# design.net
KiCad netlist of a schematic drawn in Altium Designer
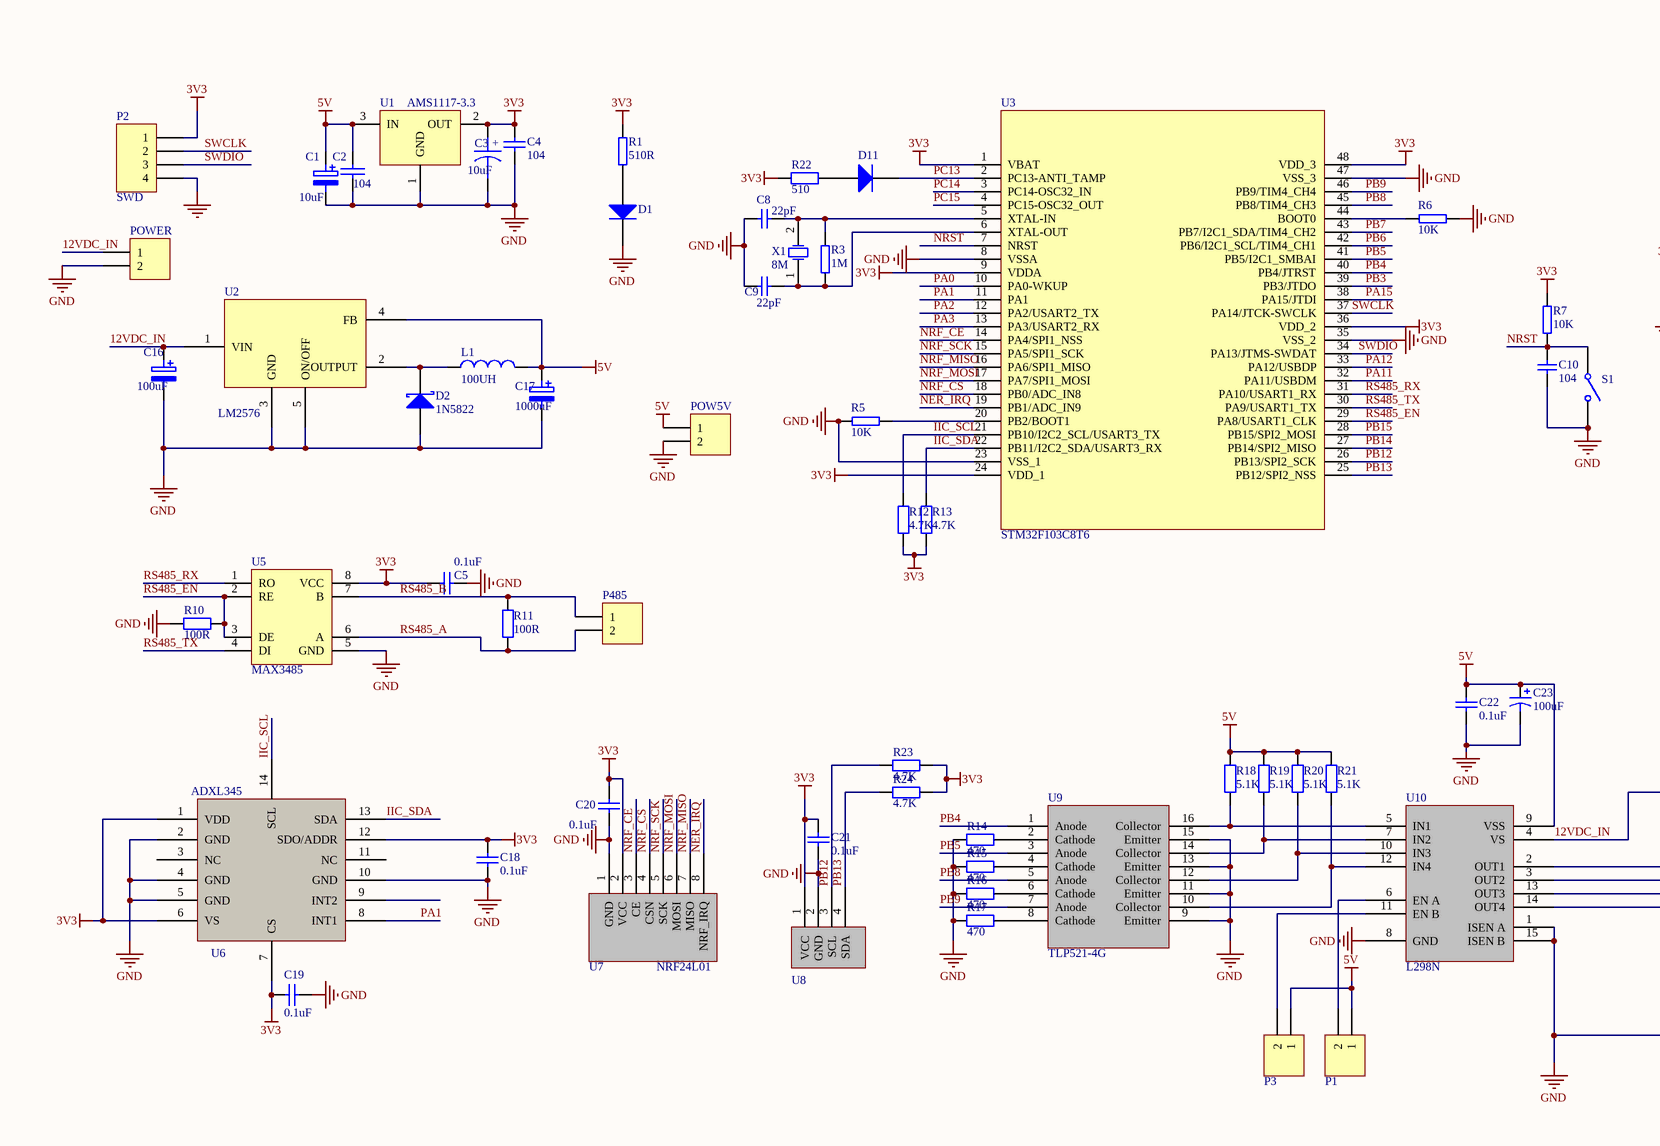
[diagram p0: 智能小车.SchDoc, left]
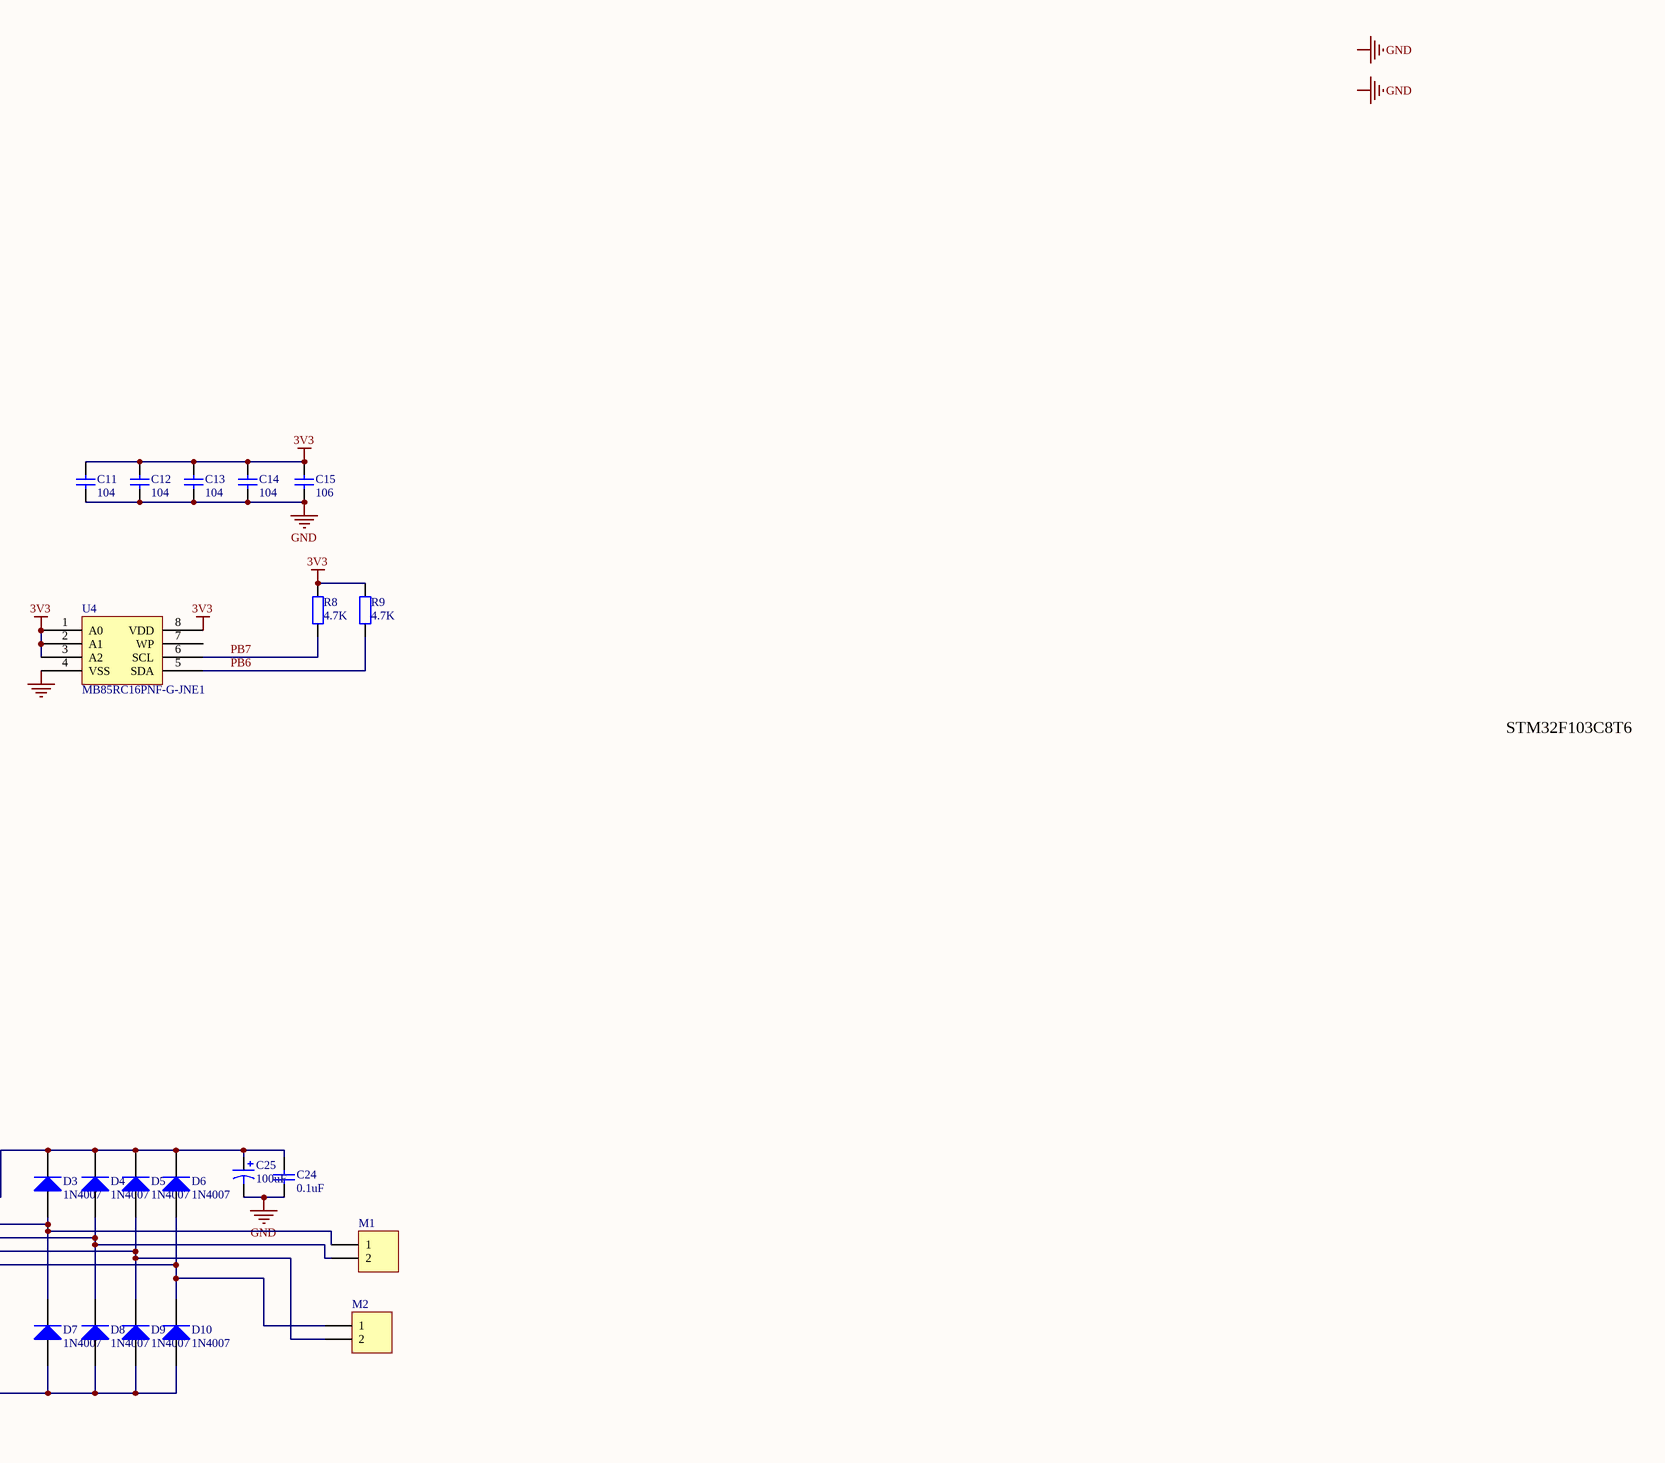
[diagram p1: 智能小车.SchDoc, right]

(export (version "E")
  (design (tool "Eeschema 10.0.6"))
  (components
    (comp (ref "C1") (value "10uF") (footprint "3216") (libsource (lib "*") (part "ELECTRO2")))
    (comp (ref "C2")
      (value "104")
      (footprint "0805")
      (description "Capacitor")
      (libsource (lib "*") (part "CAP"))
    )
    (comp (ref "C3")
      (value "10uF")
      (footprint "3216")
      (description "Capacitor")
      (libsource (lib "*") (part "CAPACITOR POL"))
    )
    (comp (ref "C4")
      (value "104")
      (footprint "0805")
      (description "Capacitor")
      (fields (field (name "PUBLISHER") "Altium Limited"))
      (libsource (lib "*") (part "Cap"))
    )
    (comp (ref "C5")
      (value "0.1uF")
      (footprint "0805")
      (description "Capacitor")
      (fields (field (name "Comment") "无源贴片电容") (field (name "PUBLISHER") "Altium Limited"))
      (libsource (lib "Miscellaneous Devices") (part "Cap"))
    )
    (comp (ref "C8")
      (value "22pF")
      (footprint "0805")
      (description "Capacitor")
      (fields (field (name "PUBLISHER") "ZL_A0OFFICE"))
      (libsource (lib "CommomDevices") (part "CAP1"))
    )
    (comp (ref "C9")
      (value "22pF")
      (footprint "0805")
      (description "Capacitor")
      (fields (field (name "PUBLISHER") "ZL_A0OFFICE"))
      (libsource (lib "CommomDevices") (part "CAP1"))
    )
    (comp (ref "C10")
      (value "104")
      (footprint "0805")
      (description "Capacitor")
      (fields (field (name "PUBLISHER") "ZL_A0OFFICE"))
      (libsource (lib "CommomDevices") (part "CAP1"))
    )
    (comp (ref "C11")
      (value "104")
      (footprint "0805")
      (description "Capacitor")
      (fields (field (name "PUBLISHER") "ZL_A0OFFICE"))
      (libsource (lib "CommomDevices") (part "CAP1"))
    )
    (comp (ref "C12")
      (value "104")
      (footprint "0805")
      (description "Capacitor")
      (fields (field (name "PUBLISHER") "ZL_A0OFFICE"))
      (libsource (lib "CommomDevices") (part "CAP1"))
    )
    (comp (ref "C13")
      (value "104")
      (footprint "0805")
      (description "Capacitor")
      (fields (field (name "PUBLISHER") "ZL_A0OFFICE"))
      (libsource (lib "CommomDevices") (part "CAP1"))
    )
    (comp (ref "C14")
      (value "104")
      (footprint "0805")
      (description "Capacitor")
      (fields (field (name "PUBLISHER") "ZL_A0OFFICE"))
      (libsource (lib "CommomDevices") (part "CAP1"))
    )
    (comp (ref "C15")
      (value "106")
      (footprint "0805")
      (description "Capacitor")
      (fields (field (name "PUBLISHER") "ZL_A0OFFICE"))
      (libsource (lib "CommomDevices") (part "CAP1"))
    )
    (comp (ref "C16") (value "100uF") (footprint "DIP2SMD") (libsource (lib "*") (part "ELECTRO2")))
    (comp (ref "C17") (value "1000uF") (footprint "DIP2SMD") (libsource (lib "*") (part "ELECTRO2")))
    (comp (ref "C18")
      (value "0.1uF")
      (footprint "0805")
      (description "Capacitor")
      (fields (field (name "Comment") "无源贴片电容") (field (name "PUBLISHER") "Altium Limited"))
      (libsource (lib "Miscellaneous Devices") (part "Cap"))
    )
    (comp (ref "C19")
      (value "0.1uF")
      (footprint "0805")
      (description "Capacitor")
      (fields (field (name "Comment") "无源贴片电容") (field (name "PUBLISHER") "Altium Limited"))
      (libsource (lib "Miscellaneous Devices") (part "Cap"))
    )
    (comp (ref "C20")
      (value "0.1uF")
      (footprint "0805")
      (description "Capacitor")
      (fields (field (name "Comment") "无源贴片电容") (field (name "PUBLISHER") "Altium Limited"))
      (libsource (lib "Miscellaneous Devices") (part "Cap"))
    )
    (comp (ref "C21")
      (value "0.1uF")
      (footprint "0805")
      (description "Capacitor")
      (fields (field (name "Comment") "无源贴片电容") (field (name "PUBLISHER") "Altium Limited"))
      (libsource (lib "Miscellaneous Devices") (part "Cap"))
    )
    (comp (ref "C22")
      (value "0.1uF")
      (footprint "0805")
      (description "Capacitor")
      (fields (field (name "Comment") "无源贴片电容") (field (name "PUBLISHER") "Altium Limited"))
      (libsource (lib "Miscellaneous Devices") (part "Cap"))
    )
    (comp (ref "C23")
      (value "100uF")
      (footprint "DIP2SMD")
      (description "Polarized Capacitor (Radial)")
      (fields (field (name "Comment") "Cap Pol1") (field (name "PUBLISHER") "Altium Limited"))
      (libsource (lib "Miscellaneous Devices") (part "Cap Pol1"))
    )
    (comp (ref "C24")
      (value "0.1uF")
      (footprint "0805")
      (description "Capacitor")
      (fields (field (name "Comment") "无源贴片电容") (field (name "PUBLISHER") "Altium Limited"))
      (libsource (lib "Miscellaneous Devices") (part "Cap"))
    )
    (comp (ref "C25")
      (value "100uF")
      (footprint "DIP2SMD")
      (description "Polarized Capacitor (Radial)")
      (fields (field (name "Comment") "Cap Pol1") (field (name "PUBLISHER") "Altium Limited"))
      (libsource (lib "Miscellaneous Devices") (part "Cap Pol1"))
    )
    (comp (ref "D1")
      (value "Diode")
      (footprint "LED")
      (description "Default Diode")
      (fields (field (name "PUBLISHER") "Altium Limited"))
      (libsource (lib "Miscellaneous Devices") (part "Diode"))
    )
    (comp (ref "D2")
      (value "1N5822")
      (footprint "DO-204AL")
      (description "Schottky Rectifier")
      (fields (field (name "PUBLISHER") "Altium Limited"))
      (libsource (lib "Miscellaneous Devices") (part "Diode 11DQ03"))
    )
    (comp (ref "D3")
      (value "1N4007")
      (footprint "DO-41")
      (description "1 Amp General Purpose Rectifier")
      (fields (field (name "PUBLISHER") "Altium Limited"))
      (libsource (lib "Miscellaneous Devices") (part "Diode 1N4007"))
    )
    (comp (ref "D4")
      (value "1N4007")
      (footprint "DO-41")
      (description "1 Amp General Purpose Rectifier")
      (fields (field (name "PUBLISHER") "Altium Limited"))
      (libsource (lib "Miscellaneous Devices") (part "Diode 1N4007"))
    )
    (comp (ref "D5")
      (value "1N4007")
      (footprint "DO-41")
      (description "1 Amp General Purpose Rectifier")
      (fields (field (name "PUBLISHER") "Altium Limited"))
      (libsource (lib "Miscellaneous Devices") (part "Diode 1N4007"))
    )
    (comp (ref "D6")
      (value "1N4007")
      (footprint "DO-41")
      (description "1 Amp General Purpose Rectifier")
      (fields (field (name "PUBLISHER") "Altium Limited"))
      (libsource (lib "Miscellaneous Devices") (part "Diode 1N4007"))
    )
    (comp (ref "D7")
      (value "1N4007")
      (footprint "DO-41")
      (description "1 Amp General Purpose Rectifier")
      (fields (field (name "PUBLISHER") "Altium Limited"))
      (libsource (lib "Miscellaneous Devices") (part "Diode 1N4007"))
    )
    (comp (ref "D8")
      (value "1N4007")
      (footprint "DO-41")
      (description "1 Amp General Purpose Rectifier")
      (fields (field (name "PUBLISHER") "Altium Limited"))
      (libsource (lib "Miscellaneous Devices") (part "Diode 1N4007"))
    )
    (comp (ref "D9")
      (value "1N4007")
      (footprint "DO-41")
      (description "1 Amp General Purpose Rectifier")
      (fields (field (name "PUBLISHER") "Altium Limited"))
      (libsource (lib "Miscellaneous Devices") (part "Diode 1N4007"))
    )
    (comp (ref "D10")
      (value "1N4007")
      (footprint "DO-41")
      (description "1 Amp General Purpose Rectifier")
      (fields (field (name "PUBLISHER") "Altium Limited"))
      (libsource (lib "Miscellaneous Devices") (part "Diode 1N4007"))
    )
    (comp (ref "D11")
      (value "Diode")
      (footprint "LED")
      (description "Default Diode")
      (fields (field (name "PUBLISHER") "Altium Limited"))
      (libsource (lib "Miscellaneous Devices") (part "Diode"))
    )
    (comp (ref "L1")
      (value "100UH")
      (footprint "L")
      (description "Inductor")
      (fields (field (name "PUBLISHER") "Altium Limited"))
      (libsource (lib "Miscellaneous Devices") (part "Inductor"))
    )
    (comp (ref "M1")
      (value "Header 2")
      (footprint "端子")
      (description "Header, 2-Pin")
      (fields (field (name "PUBLISHER") "Altium Limited"))
      (libsource (lib "Miscellaneous Connectors") (part "Header 2"))
    )
    (comp (ref "M2")
      (value "Header 2")
      (footprint "端子")
      (description "Header, 2-Pin")
      (fields (field (name "PUBLISHER") "Altium Limited"))
      (libsource (lib "Miscellaneous Connectors") (part "Header 2"))
    )
    (comp (ref "P1")
      (value "Header 2")
      (footprint "HDR1X2")
      (description "Header, 2-Pin")
      (fields (field (name "PUBLISHER") "Altium Limited"))
      (libsource (lib "") (part "Header 2_1"))
    )
    (comp (ref "P2")
      (value "SWD")
      (footprint "HDR1X4")
      (description "Header, 4-Pin, Right Angle")
      (fields (field (name "PUBLISHER") "Altium Limited"))
      (libsource (lib "*") (part "Header 4H"))
    )
    (comp (ref "P3")
      (value "Header 2")
      (footprint "HDR1X2")
      (description "Header, 2-Pin")
      (fields (field (name "PUBLISHER") "Altium Limited"))
      (libsource (lib "") (part "Header 2_1"))
    )
    (comp (ref "P485")
      (value "Header 2")
      (footprint "端子")
      (description "Header, 2-Pin")
      (fields (field (name "PUBLISHER") "Altium Limited"))
      (libsource (lib "Miscellaneous Connectors") (part "Header 2"))
    )
    (comp (ref "POW5V")
      (value "Header 2")
      (footprint "端子")
      (description "Header, 2-Pin")
      (fields (field (name "PUBLISHER") "Altium Limited"))
      (libsource (lib "Miscellaneous Connectors") (part "Header 2"))
    )
    (comp (ref "POWER")
      (value "Header 2")
      (footprint "端子")
      (description "Header, 2-Pin")
      (fields (field (name "PUBLISHER") "Altium Limited"))
      (libsource (lib "Miscellaneous Connectors") (part "Header 2"))
    )
    (comp (ref "R1") (value "510R") (footprint "0805") (libsource (lib "ZIBO V2.0_Main") (part "R")))
    (comp (ref "R3") (value "1M") (footprint "0805") (libsource (lib "ZIBO V2.0_Main") (part "R")))
    (comp (ref "R5") (value "10K") (footprint "0805") (libsource (lib "ZIBO V2.0_Main") (part "R")))
    (comp (ref "R6") (value "10K") (footprint "0805") (libsource (lib "ZIBO V2.0_Main") (part "R")))
    (comp (ref "R7") (value "10K") (footprint "0805") (libsource (lib "ZIBO V2.0_Main") (part "R")))
    (comp (ref "R8")
      (value "4.7K")
      (footprint "0805")
      (description "贴片电阻 精度1%")
      (fields (field (name "PUBLISHER") "Altium Limited"))
      (libsource (lib "") (part "Res2_1"))
    )
    (comp (ref "R9")
      (value "4.7K")
      (footprint "0805")
      (description "贴片电阻 精度1%")
      (fields (field (name "PUBLISHER") "Altium Limited"))
      (libsource (lib "") (part "Res2_1"))
    )
    (comp (ref "R10")
      (value "100R")
      (footprint "0805")
      (description "Resistor")
      (fields (field (name "PUBLISHER") "Altium Limited"))
      (libsource (lib "Miscellaneous Devices") (part "Res2"))
    )
    (comp (ref "R11")
      (value "100R")
      (footprint "0805")
      (description "Resistor")
      (fields (field (name "Comment") "贴片电阻 1%") (field (name "PUBLISHER") "Altium Limited"))
      (libsource (lib "*") (part "Res2"))
    )
    (comp (ref "R12")
      (value "4.7K")
      (footprint "0805")
      (description "贴片电阻 精度1%")
      (fields (field (name "PUBLISHER") "Altium Limited"))
      (libsource (lib "") (part "Res2_1"))
    )
    (comp (ref "R13")
      (value "4.7K")
      (footprint "0805")
      (description "贴片电阻 精度1%")
      (fields (field (name "PUBLISHER") "Altium Limited"))
      (libsource (lib "") (part "Res2_3"))
    )
    (comp (ref "R14")
      (value "470")
      (footprint "0805")
      (description "贴片电阻 精度1%")
      (fields (field (name "Comment") "4.7K") (field (name "PUBLISHER") "Altium Limited"))
      (libsource (lib "Miscellaneous Devices") (part "Res2"))
    )
    (comp (ref "R15")
      (value "470")
      (footprint "0805")
      (description "贴片电阻 精度1%")
      (fields (field (name "Comment") "4.7K") (field (name "PUBLISHER") "Altium Limited"))
      (libsource (lib "Miscellaneous Devices") (part "Res2"))
    )
    (comp (ref "R16")
      (value "470")
      (footprint "0805")
      (description "贴片电阻 精度1%")
      (fields (field (name "Comment") "4.7K") (field (name "PUBLISHER") "Altium Limited"))
      (libsource (lib "Miscellaneous Devices") (part "Res2"))
    )
    (comp (ref "R17")
      (value "470")
      (footprint "0805")
      (description "贴片电阻 精度1%")
      (fields (field (name "Comment") "4.7K") (field (name "PUBLISHER") "Altium Limited"))
      (libsource (lib "Miscellaneous Devices") (part "Res2"))
    )
    (comp (ref "R18")
      (value "5.1K")
      (footprint "0805")
      (description "贴片电阻 精度1%")
      (fields (field (name "Comment") "4.7K") (field (name "PUBLISHER") "Altium Limited"))
      (libsource (lib "") (part "Res2_1"))
    )
    (comp (ref "R19")
      (value "5.1K")
      (footprint "0805")
      (description "贴片电阻 精度1%")
      (fields (field (name "Comment") "4.7K") (field (name "PUBLISHER") "Altium Limited"))
      (libsource (lib "") (part "Res2_1"))
    )
    (comp (ref "R20")
      (value "5.1K")
      (footprint "0805")
      (description "贴片电阻 精度1%")
      (fields (field (name "Comment") "4.7K") (field (name "PUBLISHER") "Altium Limited"))
      (libsource (lib "") (part "Res2_1"))
    )
    (comp (ref "R21")
      (value "5.1K")
      (footprint "0805")
      (description "贴片电阻 精度1%")
      (fields (field (name "Comment") "4.7K") (field (name "PUBLISHER") "Altium Limited"))
      (libsource (lib "") (part "Res2_1"))
    )
    (comp (ref "R22")
      (value "510")
      (footprint "0805")
      (description "Resistor")
      (fields (field (name "Comment") "Res2") (field (name "PUBLISHER") "Altium Limited"))
      (libsource (lib "Miscellaneous Devices") (part "Res2"))
    )
    (comp (ref "R23")
      (value "4.7K")
      (footprint "0805")
      (description "贴片电阻 精度1%")
      (fields (field (name "PUBLISHER") "Altium Limited"))
      (libsource (lib "") (part "Res2_2"))
    )
    (comp (ref "R24")
      (value "4.7K")
      (footprint "0805")
      (description "贴片电阻 精度1%")
      (fields (field (name "PUBLISHER") "Altium Limited"))
      (libsource (lib "") (part "Res2_2"))
    )
    (comp (ref "S1")
      (value "SW-SPST")
      (footprint "SWITCH")
      (description "Single-Pole, Single-Throw Switch")
      (libsource (lib "Miscellaneous Devices") (part "SW-SPST"))
    )
    (comp (ref "U1")
      (value "AMS1117-3.3")
      (footprint "SOT223")
      (libsource (lib "Newcapec9263_Board_NEW") (part "LT1085CM-3.3"))
    )
    (comp (ref "U2") (value "LM2576") (footprint "LM2576") (libsource (lib "Schlib1") (part "LM2576")))
    (comp (ref "U3")
      (value "STM32F103C8T6")
      (footprint "STM32F103C8T6")
      (libsource (lib "STM32_Smart") (part "STM32F103C8T6"))
    )
    (comp (ref "U4")
      (value "MB85RC16PNF-G-JNE1")
      (footprint "SO-8")
      (description "EEPROM存储")
      (libsource (lib "*") (part "MB85RC16PNF-G-JNE1"))
    )
    (comp (ref "U5")
      (value "MAX3485")
      (footprint "SO-8")
      (description "485总线芯片")
      (libsource (lib "Fszhang") (part "SP3485"))
    )
    (comp (ref "U6")
      (value "ADXL345")
      (footprint "LGA14-ADXL345")
      (libsource (lib "Schlib1") (part "ADXL345"))
    )
    (comp (ref "U7") (value "NRF24L01") (footprint "NRF24L01") (libsource (lib "Schlib1") (part "NRF24L01")))
    (comp (ref "U8") (value "OLED") (footprint "IDCD4") (libsource (lib "Schlib1") (part "OLED")))
    (comp (ref "U9") (value "TLP521-4G") (footprint "SOP-16") (libsource (lib "Schlib1") (part "TLP521-4G")))
    (comp (ref "U10") (value "L298N") (footprint "L298N") (libsource (lib "Schlib1") (part "L298N")))
    (comp (ref "X1")
      (value "8M")
      (footprint "晶振")
      (description "Crystal Oscillator")
      (fields (field (name "PUBLISHER") "ZL_A0OFFICE"))
      (libsource (lib "CommomDevices") (part "XTAL_SMD"))
    )
  )
  (nets
    (net (code "1") (name "/12VDC_IN") (class "Default")
      (node (ref "C16") (pin "1") (pintype "passive"))
      (node (ref "C24") (pin "2") (pinfunction "2_2") (pintype "passive"))
      (node (ref "C25") (pin "1") (pinfunction "1_1") (pintype "passive"))
      (node (ref "D3") (pin "2") (pinfunction "K_2") (pintype "passive"))
      (node (ref "D4") (pin "2") (pinfunction "K_2") (pintype "passive"))
      (node (ref "D5") (pin "2") (pinfunction "K_2") (pintype "passive"))
      (node (ref "D6") (pin "2") (pinfunction "K_2") (pintype "passive"))
      (node (ref "POWER") (pin "1") (pinfunction "1_1") (pintype "passive"))
      (node (ref "U10") (pin "4") (pinfunction "VS_4") (pintype "passive"))
      (node (ref "U2") (pin "1") (pinfunction "VIN_1") (pintype "passive"))
    )
    (net (code "2") (name "/IIC_SCL") (class "Default")
      (node (ref "R12") (pin "2") (pinfunction "2_2") (pintype "passive"))
      (node (ref "U3") (pin "21") (pinfunction "PB10/I2C2_SCL/USART3_TX_21") (pintype "passive"))
      (node (ref "U6") (pin "14") (pinfunction "SCL_14") (pintype "passive"))
    )
    (net (code "3") (name "/IIC_SDA") (class "Default")
      (node (ref "R13") (pin "1") (pinfunction "1_1") (pintype "passive"))
      (node (ref "U3") (pin "22") (pinfunction "PB11/I2C2_SDA/USART3_RX_22") (pintype "passive"))
      (node (ref "U6") (pin "13") (pinfunction "SDA_13") (pintype "passive"))
    )
    (net (code "4") (name "/NER_IRQ") (class "Default")
      (node (ref "U3") (pin "19") (pinfunction "PB1/ADC_IN9_19") (pintype "passive"))
      (node (ref "U7") (pin "8") (pinfunction "NRF_IRQ_8") (pintype "passive"))
    )
    (net (code "5") (name "/NRF_CE") (class "Default")
      (node (ref "U3") (pin "14") (pinfunction "PA4/SPI1_NSS_14") (pintype "passive"))
      (node (ref "U7") (pin "3") (pinfunction "CE_3") (pintype "passive"))
    )
    (net (code "6") (name "/NRF_CS") (class "Default")
      (node (ref "U3") (pin "18") (pinfunction "PB0/ADC_IN8_18") (pintype "passive"))
      (node (ref "U7") (pin "4") (pinfunction "CSN_4") (pintype "passive"))
    )
    (net (code "7") (name "/NRF_MISO") (class "Default")
      (node (ref "U3") (pin "16") (pinfunction "PA6/SPI1_MISO_16") (pintype "passive"))
      (node (ref "U7") (pin "7") (pinfunction "MISO_7") (pintype "passive"))
    )
    (net (code "8") (name "/NRF_MOSI") (class "Default")
      (node (ref "U3") (pin "17") (pinfunction "PA7/SPI1_MOSI_17") (pintype "passive"))
      (node (ref "U7") (pin "6") (pinfunction "MOSI_6") (pintype "passive"))
    )
    (net (code "9") (name "/NRF_SCK") (class "Default")
      (node (ref "U3") (pin "15") (pinfunction "PA5/SPI1_SCK_15") (pintype "passive"))
      (node (ref "U7") (pin "5") (pinfunction "SCK_5") (pintype "passive"))
    )
    (net (code "10") (name "/NRST") (class "Default")
      (node (ref "C10") (pin "1") (pinfunction "1_1") (pintype "passive"))
      (node (ref "R7") (pin "1") (pinfunction "1_1") (pintype "passive"))
      (node (ref "S1") (pin "1") (pinfunction "COMMON_1") (pintype "passive"))
      (node (ref "U3") (pin "7") (pinfunction "NRST_7") (pintype "passive"))
    )
    (net (code "11") (name "/PA0") (class "Default")
      (node (ref "U3") (pin "10") (pinfunction "PA0-WKUP_10") (pintype "passive"))
    )
    (net (code "12") (name "/PA1") (class "Default")
      (node (ref "U3") (pin "11") (pinfunction "PA1_11") (pintype "passive"))
      (node (ref "U6") (pin "8") (pinfunction "INT1_8") (pintype "passive"))
    )
    (net (code "13") (name "/PA2") (class "Default")
      (node (ref "U3") (pin "12") (pinfunction "PA2/USART2_TX_12") (pintype "passive"))
    )
    (net (code "14") (name "/PA3") (class "Default")
      (node (ref "U3") (pin "13") (pinfunction "PA3/USART2_RX_13") (pintype "passive"))
    )
    (net (code "15") (name "/PA11") (class "Default")
      (node (ref "U3") (pin "32") (pinfunction "PA11/USBDM_32") (pintype "passive"))
    )
    (net (code "16") (name "/PA12") (class "Default")
      (node (ref "U3") (pin "33") (pinfunction "PA12/USBDP_33") (pintype "passive"))
    )
    (net (code "17") (name "/PA15") (class "Default")
      (node (ref "U3") (pin "38") (pinfunction "PA15/JTDI_38") (pintype "passive"))
    )
    (net (code "18") (name "/PB3") (class "Default")
      (node (ref "U3") (pin "39") (pinfunction "PB3/JTDO_39") (pintype "passive"))
    )
    (net (code "19") (name "/PB4") (class "Default")
      (node (ref "U3") (pin "40") (pinfunction "PB4/JTRST_40") (pintype "passive"))
      (node (ref "U9") (pin "1") (pinfunction "Anode_1") (pintype "passive"))
    )
    (net (code "20") (name "/PB5") (class "Default")
      (node (ref "U3") (pin "41") (pinfunction "PB5/I2C1_SMBAI_41") (pintype "passive"))
      (node (ref "U9") (pin "3") (pinfunction "Anode_3") (pintype "passive"))
    )
    (net (code "21") (name "/PB6") (class "Default")
      (node (ref "R9") (pin "1") (pinfunction "1_1") (pintype "passive"))
      (node (ref "U3") (pin "42") (pinfunction "PB6/I2C1_SCL/TIM4_CH1_42") (pintype "passive"))
      (node (ref "U4") (pin "5") (pinfunction "SDA_5") (pintype "passive"))
    )
    (net (code "22") (name "/PB7") (class "Default")
      (node (ref "R8") (pin "1") (pinfunction "1_1") (pintype "passive"))
      (node (ref "U3") (pin "43") (pinfunction "PB7/I2C1_SDA/TIM4_CH2_43") (pintype "passive"))
      (node (ref "U4") (pin "6") (pinfunction "SCL_6") (pintype "passive"))
    )
    (net (code "23") (name "/PB8") (class "Default")
      (node (ref "U3") (pin "45") (pinfunction "PB8/TIM4_CH3_45") (pintype "passive"))
      (node (ref "U9") (pin "5") (pinfunction "Anode_5") (pintype "passive"))
    )
    (net (code "24") (name "/PB9") (class "Default")
      (node (ref "U3") (pin "46") (pinfunction "PB9/TIM4_CH4_46") (pintype "passive"))
      (node (ref "U9") (pin "7") (pinfunction "Anode_7") (pintype "passive"))
    )
    (net (code "25") (name "/PB12") (class "Default")
      (node (ref "R23") (pin "2") (pinfunction "2_2") (pintype "passive"))
      (node (ref "U3") (pin "26") (pinfunction "PB13/SPI2_SCK_26") (pintype "passive"))
      (node (ref "U8") (pin "3") (pinfunction "SCL_3") (pintype "passive"))
    )
    (net (code "26") (name "/PB13") (class "Default")
      (node (ref "R24") (pin "2") (pinfunction "2_2") (pintype "passive"))
      (node (ref "U3") (pin "25") (pinfunction "PB12/SPI2_NSS_25") (pintype "passive"))
      (node (ref "U8") (pin "4") (pinfunction "SDA_4") (pintype "passive"))
    )
    (net (code "27") (name "/PB14") (class "Default")
      (node (ref "U3") (pin "27") (pinfunction "PB14/SPI2_MISO_27") (pintype "passive"))
    )
    (net (code "28") (name "/PB15") (class "Default")
      (node (ref "U3") (pin "28") (pinfunction "PB15/SPI2_MOSI_28") (pintype "passive"))
    )
    (net (code "29") (name "/PC13") (class "Default")
      (node (ref "D11") (pin "2") (pinfunction "K_2") (pintype "passive"))
      (node (ref "U3") (pin "2") (pinfunction "PC13-ANTI_TAMP_2") (pintype "passive"))
    )
    (net (code "30") (name "/PC14") (class "Default")
      (node (ref "U3") (pin "3") (pinfunction "PC14-OSC32_IN_3") (pintype "passive"))
    )
    (net (code "31") (name "/PC15") (class "Default")
      (node (ref "U3") (pin "4") (pinfunction "PC15-OSC32_OUT_4") (pintype "passive"))
    )
    (net (code "32") (name "/RS485_A") (class "Default")
      (node (ref "P485") (pin "2") (pinfunction "2_2") (pintype "passive"))
      (node (ref "R11") (pin "1") (pinfunction "1_1") (pintype "passive"))
      (node (ref "U5") (pin "6") (pinfunction "A_6") (pintype "passive"))
    )
    (net (code "33") (name "/RS485_B") (class "Default")
      (node (ref "P485") (pin "1") (pinfunction "1_1") (pintype "passive"))
      (node (ref "R11") (pin "2") (pinfunction "2_2") (pintype "passive"))
      (node (ref "U5") (pin "7") (pinfunction "B_7") (pintype "passive"))
    )
    (net (code "34") (name "/RS485_EN") (class "Default")
      (node (ref "R10") (pin "2") (pinfunction "2_2") (pintype "passive"))
      (node (ref "U3") (pin "29") (pinfunction "PA8/USART1_CLK_29") (pintype "passive"))
      (node (ref "U5") (pin "2") (pinfunction "RE_2") (pintype "passive"))
      (node (ref "U5") (pin "3") (pinfunction "DE_3") (pintype "passive"))
    )
    (net (code "35") (name "/RS485_RX") (class "Default")
      (node (ref "U3") (pin "31") (pinfunction "PA10/USART1_RX_31") (pintype "passive"))
      (node (ref "U5") (pin "1") (pinfunction "RO_1") (pintype "passive"))
    )
    (net (code "36") (name "/RS485_TX") (class "Default")
      (node (ref "U3") (pin "30") (pinfunction "PA9/USART1_TX_30") (pintype "passive"))
      (node (ref "U5") (pin "4") (pinfunction "DI_4") (pintype "passive"))
    )
    (net (code "37") (name "/SWCLK") (class "Default")
      (node (ref "P2") (pin "2") (pinfunction "2_2") (pintype "passive"))
      (node (ref "U3") (pin "37") (pinfunction "PA14/JTCK-SWCLK_37") (pintype "passive"))
    )
    (net (code "38") (name "/SWDIO") (class "Default")
      (node (ref "P2") (pin "3") (pinfunction "3_3") (pintype "passive"))
      (node (ref "U3") (pin "34") (pinfunction "PA13/JTMS-SWDAT_34") (pintype "passive"))
    )
    (net (code "39") (name "3V3") (class "Default")
      (node (ref "C11") (pin "1") (pinfunction "1_1") (pintype "passive"))
      (node (ref "C12") (pin "1") (pinfunction "1_1") (pintype "passive"))
      (node (ref "C13") (pin "1") (pinfunction "1_1") (pintype "passive"))
      (node (ref "C14") (pin "1") (pinfunction "1_1") (pintype "passive"))
      (node (ref "C15") (pin "1") (pinfunction "1_1") (pintype "passive"))
      (node (ref "C18") (pin "1") (pinfunction "1_1") (pintype "passive"))
      (node (ref "C19") (pin "2") (pinfunction "2_2") (pintype "passive"))
      (node (ref "C20") (pin "1") (pinfunction "1_1") (pintype "passive"))
      (node (ref "C21") (pin "2") (pinfunction "2_2") (pintype "passive"))
      (node (ref "C3") (pin "1") (pinfunction "1_1") (pintype "passive"))
      (node (ref "C4") (pin "1") (pinfunction "1_1") (pintype "passive"))
      (node (ref "C5") (pin "1") (pinfunction "1_1") (pintype "passive"))
      (node (ref "P2") (pin "1") (pinfunction "1_1") (pintype "passive"))
      (node (ref "R1") (pin "2") (pinfunction "2_2") (pintype "passive"))
      (node (ref "R12") (pin "1") (pinfunction "1_1") (pintype "passive"))
      (node (ref "R13") (pin "2") (pinfunction "2_2") (pintype "passive"))
      (node (ref "R22") (pin "1") (pinfunction "1_1") (pintype "passive"))
      (node (ref "R23") (pin "1") (pinfunction "1_1") (pintype "passive"))
      (node (ref "R24") (pin "1") (pinfunction "1_1") (pintype "passive"))
      (node (ref "R7") (pin "2") (pinfunction "2_2") (pintype "passive"))
      (node (ref "R8") (pin "2") (pinfunction "2_2") (pintype "passive"))
      (node (ref "R9") (pin "2") (pinfunction "2_2") (pintype "passive"))
      (node (ref "U1") (pin "2") (pinfunction "OUT_2") (pintype "passive"))
      (node (ref "U3") (pin "1") (pinfunction "VBAT_1") (pintype "passive"))
      (node (ref "U3") (pin "24") (pinfunction "VDD_1_24") (pintype "passive"))
      (node (ref "U3") (pin "36") (pinfunction "VDD_2_36") (pintype "passive"))
      (node (ref "U3") (pin "48") (pinfunction "VDD_3_48") (pintype "passive"))
      (node (ref "U3") (pin "9") (pinfunction "VDDA_9") (pintype "passive"))
      (node (ref "U4") (pin "1") (pinfunction "A0_1") (pintype "passive"))
      (node (ref "U4") (pin "2") (pinfunction "A1_2") (pintype "passive"))
      (node (ref "U4") (pin "3") (pinfunction "A2_3") (pintype "passive"))
      (node (ref "U4") (pin "8") (pinfunction "VDD_8") (pintype "passive"))
      (node (ref "U5") (pin "8") (pinfunction "VCC_8") (pintype "passive"))
      (node (ref "U6") (pin "1") (pinfunction "VDD_1") (pintype "passive"))
      (node (ref "U6") (pin "12") (pinfunction "SDO/ADDR_12") (pintype "passive"))
      (node (ref "U6") (pin "6") (pinfunction "VS_6") (pintype "passive"))
      (node (ref "U6") (pin "7") (pinfunction "CS_7") (pintype "passive"))
      (node (ref "U7") (pin "2") (pinfunction "VCC_2") (pintype "passive"))
      (node (ref "U8") (pin "1") (pinfunction "VCC_1") (pintype "passive"))
    )
    (net (code "40") (name "5V") (class "Default")
      (node (ref "C1") (pin "1") (pintype "passive"))
      (node (ref "C17") (pin "1") (pintype "passive"))
      (node (ref "C2") (pin "1") (pinfunction "1_1") (pintype "passive"))
      (node (ref "C22") (pin "2") (pinfunction "2_2") (pintype "passive"))
      (node (ref "C23") (pin "1") (pinfunction "1_1") (pintype "passive"))
      (node (ref "L1") (pin "2") (pinfunction "2_2") (pintype "passive"))
      (node (ref "P1") (pin "1") (pinfunction "1_1") (pintype "passive"))
      (node (ref "P3") (pin "1") (pinfunction "1_1") (pintype "passive"))
      (node (ref "POW5V") (pin "1") (pinfunction "1_1") (pintype "passive"))
      (node (ref "R18") (pin "2") (pinfunction "2_2") (pintype "passive"))
      (node (ref "R19") (pin "2") (pinfunction "2_2") (pintype "passive"))
      (node (ref "R20") (pin "2") (pinfunction "2_2") (pintype "passive"))
      (node (ref "R21") (pin "2") (pinfunction "2_2") (pintype "passive"))
      (node (ref "U1") (pin "3") (pinfunction "IN_3") (pintype "passive"))
      (node (ref "U10") (pin "9") (pinfunction "VSS_9") (pintype "passive"))
      (node (ref "U2") (pin "4") (pinfunction "FB_4") (pintype "passive"))
    )
    (net (code "41") (name "GND") (class "Default")
      (node (ref "C1") (pin "2") (pintype "passive"))
      (node (ref "C10") (pin "2") (pinfunction "2_2") (pintype "passive"))
      (node (ref "C11") (pin "2") (pinfunction "2_2") (pintype "passive"))
      (node (ref "C12") (pin "2") (pinfunction "2_2") (pintype "passive"))
      (node (ref "C13") (pin "2") (pinfunction "2_2") (pintype "passive"))
      (node (ref "C14") (pin "2") (pinfunction "2_2") (pintype "passive"))
      (node (ref "C15") (pin "2") (pinfunction "2_2") (pintype "passive"))
      (node (ref "C16") (pin "2") (pintype "passive"))
      (node (ref "C17") (pin "2") (pintype "passive"))
      (node (ref "C18") (pin "2") (pinfunction "2_2") (pintype "passive"))
      (node (ref "C19") (pin "1") (pinfunction "1_1") (pintype "passive"))
      (node (ref "C2") (pin "2") (pinfunction "2_2") (pintype "passive"))
      (node (ref "C20") (pin "2") (pinfunction "2_2") (pintype "passive"))
      (node (ref "C21") (pin "1") (pinfunction "1_1") (pintype "passive"))
      (node (ref "C22") (pin "1") (pinfunction "1_1") (pintype "passive"))
      (node (ref "C23") (pin "2") (pinfunction "2_2") (pintype "passive"))
      (node (ref "C24") (pin "1") (pinfunction "1_1") (pintype "passive"))
      (node (ref "C25") (pin "2") (pinfunction "2_2") (pintype "passive"))
      (node (ref "C3") (pin "2") (pinfunction "2_2") (pintype "passive"))
      (node (ref "C4") (pin "2") (pinfunction "2_2") (pintype "passive"))
      (node (ref "C5") (pin "2") (pinfunction "2_2") (pintype "passive"))
      (node (ref "C8") (pin "2") (pinfunction "2_2") (pintype "passive"))
      (node (ref "C9") (pin "2") (pinfunction "2_2") (pintype "passive"))
      (node (ref "D1") (pin "2") (pinfunction "K_2") (pintype "passive"))
      (node (ref "D10") (pin "1") (pinfunction "A_1") (pintype "passive"))
      (node (ref "D2") (pin "1") (pinfunction "A_1") (pintype "passive"))
      (node (ref "D7") (pin "1") (pinfunction "A_1") (pintype "passive"))
      (node (ref "D8") (pin "1") (pinfunction "A_1") (pintype "passive"))
      (node (ref "D9") (pin "1") (pinfunction "A_1") (pintype "passive"))
      (node (ref "P2") (pin "4") (pinfunction "4_4") (pintype "passive"))
      (node (ref "POW5V") (pin "2") (pinfunction "2_2") (pintype "passive"))
      (node (ref "POWER") (pin "2") (pinfunction "2_2") (pintype "passive"))
      (node (ref "R10") (pin "1") (pinfunction "1_1") (pintype "passive"))
      (node (ref "R14") (pin "1") (pinfunction "1_1") (pintype "passive"))
      (node (ref "R15") (pin "1") (pinfunction "1_1") (pintype "passive"))
      (node (ref "R16") (pin "1") (pinfunction "1_1") (pintype "passive"))
      (node (ref "R17") (pin "1") (pinfunction "1_1") (pintype "passive"))
      (node (ref "R5") (pin "2") (pinfunction "2_2") (pintype "passive"))
      (node (ref "R6") (pin "1") (pinfunction "1_1") (pintype "passive"))
      (node (ref "S1") (pin "2") (pinfunction "NO_2") (pintype "passive"))
      (node (ref "U1") (pin "1") (pinfunction "GND_1") (pintype "passive"))
      (node (ref "U10") (pin "1") (pinfunction "ISEN_A_1") (pintype "passive"))
      (node (ref "U10") (pin "15") (pinfunction "ISEN_B_15") (pintype "passive"))
      (node (ref "U10") (pin "8") (pinfunction "GND_8") (pintype "passive"))
      (node (ref "U2") (pin "3") (pinfunction "GND_3") (pintype "passive"))
      (node (ref "U2") (pin "5") (pinfunction "ON/OFF_5") (pintype "passive"))
      (node (ref "U3") (pin "23") (pinfunction "VSS_1_23") (pintype "passive"))
      (node (ref "U3") (pin "35") (pinfunction "VSS_2_35") (pintype "passive"))
      (node (ref "U3") (pin "47") (pinfunction "VSS_3_47") (pintype "passive"))
      (node (ref "U3") (pin "8") (pinfunction "VSSA_8") (pintype "passive"))
      (node (ref "U4") (pin "4") (pinfunction "VSS_4") (pintype "passive"))
      (node (ref "U5") (pin "5") (pinfunction "GND_5") (pintype "passive"))
      (node (ref "U6") (pin "10") (pinfunction "GND_10") (pintype "passive"))
      (node (ref "U6") (pin "2") (pinfunction "GND_2") (pintype "passive"))
      (node (ref "U6") (pin "4") (pinfunction "GND_4") (pintype "passive"))
      (node (ref "U6") (pin "5") (pinfunction "GND_5") (pintype "passive"))
      (node (ref "U7") (pin "1") (pinfunction "GND_1") (pintype "passive"))
      (node (ref "U8") (pin "2") (pinfunction "GND_2") (pintype "passive"))
      (node (ref "U9") (pin "11") (pinfunction "Emitter_11") (pintype "passive"))
      (node (ref "U9") (pin "13") (pinfunction "Emitter_13") (pintype "passive"))
      (node (ref "U9") (pin "15") (pinfunction "Emitter_15") (pintype "passive"))
      (node (ref "U9") (pin "9") (pinfunction "Emitter_9") (pintype "passive"))
    )
    (net (code "42") (name "Net-(D1-A)") (class "Default")
      (node (ref "D1") (pin "1") (pinfunction "A_1") (pintype "passive"))
      (node (ref "R1") (pin "1") (pinfunction "1_1") (pintype "passive"))
    )
    (net (code "43") (name "Net-(D2-K)") (class "Default")
      (node (ref "D2") (pin "2") (pinfunction "K_2") (pintype "passive"))
      (node (ref "L1") (pin "1") (pinfunction "1_1") (pintype "passive"))
      (node (ref "U2") (pin "2") (pinfunction "OUTPUT_2") (pintype "passive"))
    )
    (net (code "44") (name "Net-(D3-A)") (class "Default")
      (node (ref "D3") (pin "1") (pinfunction "A_1") (pintype "passive"))
      (node (ref "D7") (pin "2") (pinfunction "K_2") (pintype "passive"))
      (node (ref "M1") (pin "1") (pinfunction "1_1") (pintype "passive"))
      (node (ref "U10") (pin "2") (pinfunction "OUT1_2") (pintype "passive"))
    )
    (net (code "45") (name "Net-(D4-A)") (class "Default")
      (node (ref "D4") (pin "1") (pinfunction "A_1") (pintype "passive"))
      (node (ref "D8") (pin "2") (pinfunction "K_2") (pintype "passive"))
      (node (ref "M1") (pin "2") (pinfunction "2_2") (pintype "passive"))
      (node (ref "U10") (pin "3") (pinfunction "OUT2_3") (pintype "passive"))
    )
    (net (code "46") (name "Net-(D5-A)") (class "Default")
      (node (ref "D5") (pin "1") (pinfunction "A_1") (pintype "passive"))
      (node (ref "D9") (pin "2") (pinfunction "K_2") (pintype "passive"))
      (node (ref "M2") (pin "2") (pinfunction "2_2") (pintype "passive"))
      (node (ref "U10") (pin "13") (pinfunction "OUT3_13") (pintype "passive"))
    )
    (net (code "47") (name "Net-(D10-K)") (class "Default")
      (node (ref "D10") (pin "2") (pinfunction "K_2") (pintype "passive"))
      (node (ref "D6") (pin "1") (pinfunction "A_1") (pintype "passive"))
      (node (ref "M2") (pin "1") (pinfunction "1_1") (pintype "passive"))
      (node (ref "U10") (pin "14") (pinfunction "OUT4_14") (pintype "passive"))
    )
    (net (code "48") (name "Net-(D11-A)") (class "Default")
      (node (ref "D11") (pin "1") (pinfunction "A_1") (pintype "passive"))
      (node (ref "R22") (pin "2") (pinfunction "2_2") (pintype "passive"))
    )
    (net (code "49") (name "Net-(R14-Pad2)") (class "Default")
      (node (ref "R14") (pin "2") (pinfunction "2_2") (pintype "passive"))
      (node (ref "U9") (pin "2") (pinfunction "Cathode_2") (pintype "passive"))
    )
    (net (code "50") (name "Net-(R15-Pad2)") (class "Default")
      (node (ref "R15") (pin "2") (pinfunction "2_2") (pintype "passive"))
      (node (ref "U9") (pin "4") (pinfunction "Cathode_4") (pintype "passive"))
    )
    (net (code "51") (name "Net-(R16-Pad2)") (class "Default")
      (node (ref "R16") (pin "2") (pinfunction "2_2") (pintype "passive"))
      (node (ref "U9") (pin "6") (pinfunction "Cathode_6") (pintype "passive"))
    )
    (net (code "52") (name "Net-(R17-Pad2)") (class "Default")
      (node (ref "R17") (pin "2") (pinfunction "2_2") (pintype "passive"))
      (node (ref "U9") (pin "8") (pinfunction "Cathode_8") (pintype "passive"))
    )
    (net (code "53") (name "Net-(U3-BOOT0)") (class "Default")
      (node (ref "R6") (pin "2") (pinfunction "2_2") (pintype "passive"))
      (node (ref "U3") (pin "44") (pinfunction "BOOT0_44") (pintype "passive"))
    )
    (net (code "54") (name "Net-(U3-PB2{slash}BOOT1)") (class "Default")
      (node (ref "R5") (pin "1") (pinfunction "1_1") (pintype "passive"))
      (node (ref "U3") (pin "20") (pinfunction "PB2/BOOT1_20") (pintype "passive"))
    )
    (net (code "55") (name "Net-(U3-XTAL-IN)") (class "Default")
      (node (ref "C8") (pin "1") (pinfunction "1_1") (pintype "passive"))
      (node (ref "R3") (pin "2") (pinfunction "2_2") (pintype "passive"))
      (node (ref "U3") (pin "5") (pinfunction "XTAL-IN_5") (pintype "passive"))
      (node (ref "X1") (pin "2") (pinfunction "2_2") (pintype "passive"))
    )
    (net (code "56") (name "Net-(U3-XTAL-OUT)") (class "Default")
      (node (ref "C9") (pin "1") (pinfunction "1_1") (pintype "passive"))
      (node (ref "R3") (pin "1") (pinfunction "1_1") (pintype "passive"))
      (node (ref "U3") (pin "6") (pinfunction "XTAL-OUT_6") (pintype "passive"))
      (node (ref "X1") (pin "1") (pinfunction "1_1") (pintype "passive"))
    )
    (net (code "57") (name "Net-(U10-EN_A)") (class "Default")
      (node (ref "P1") (pin "2") (pinfunction "2_2") (pintype "passive"))
      (node (ref "U10") (pin "6") (pinfunction "EN_A_6") (pintype "passive"))
    )
    (net (code "58") (name "Net-(U10-EN_B)") (class "Default")
      (node (ref "P3") (pin "2") (pinfunction "2_2") (pintype "passive"))
      (node (ref "U10") (pin "11") (pinfunction "EN_B_11") (pintype "passive"))
    )
    (net (code "59") (name "Net-(U10-IN1)") (class "Default")
      (node (ref "R18") (pin "1") (pinfunction "1_1") (pintype "passive"))
      (node (ref "U10") (pin "5") (pinfunction "IN1_5") (pintype "passive"))
      (node (ref "U9") (pin "16") (pinfunction "Collector_16") (pintype "passive"))
    )
    (net (code "60") (name "Net-(U10-IN2)") (class "Default")
      (node (ref "R19") (pin "1") (pinfunction "1_1") (pintype "passive"))
      (node (ref "U10") (pin "7") (pinfunction "IN2_7") (pintype "passive"))
      (node (ref "U9") (pin "14") (pinfunction "Collector_14") (pintype "passive"))
    )
    (net (code "61") (name "Net-(U10-IN3)") (class "Default")
      (node (ref "R20") (pin "1") (pinfunction "1_1") (pintype "passive"))
      (node (ref "U10") (pin "10") (pinfunction "IN3_10") (pintype "passive"))
      (node (ref "U9") (pin "12") (pinfunction "Collector_12") (pintype "passive"))
    )
    (net (code "62") (name "Net-(U10-IN4)") (class "Default")
      (node (ref "R21") (pin "1") (pinfunction "1_1") (pintype "passive"))
      (node (ref "U10") (pin "12") (pinfunction "IN4_12") (pintype "passive"))
      (node (ref "U9") (pin "10") (pinfunction "Collector_10") (pintype "passive"))
    )
    (net (code "63") (name "unconnected-(U4-WP-Pad7)") (class "Default")
      (node (ref "U4") (pin "7") (pinfunction "WP_7") (pintype "passive"))
    )
    (net (code "64") (name "unconnected-(U6-INT2-Pad9)") (class "Default")
      (node (ref "U6") (pin "9") (pinfunction "INT2_9") (pintype "passive"))
    )
    (net (code "65") (name "unconnected-(U6-NC-Pad3)") (class "Default")
      (node (ref "U6") (pin "3") (pinfunction "NC_3") (pintype "passive"))
    )
    (net (code "66") (name "unconnected-(U6-NC-Pad11)") (class "Default")
      (node (ref "U6") (pin "11") (pinfunction "NC_11") (pintype "passive"))
    )
  )
)
